# GatorLog.net
KiCad netlist of a schematic drawn in EAGLE
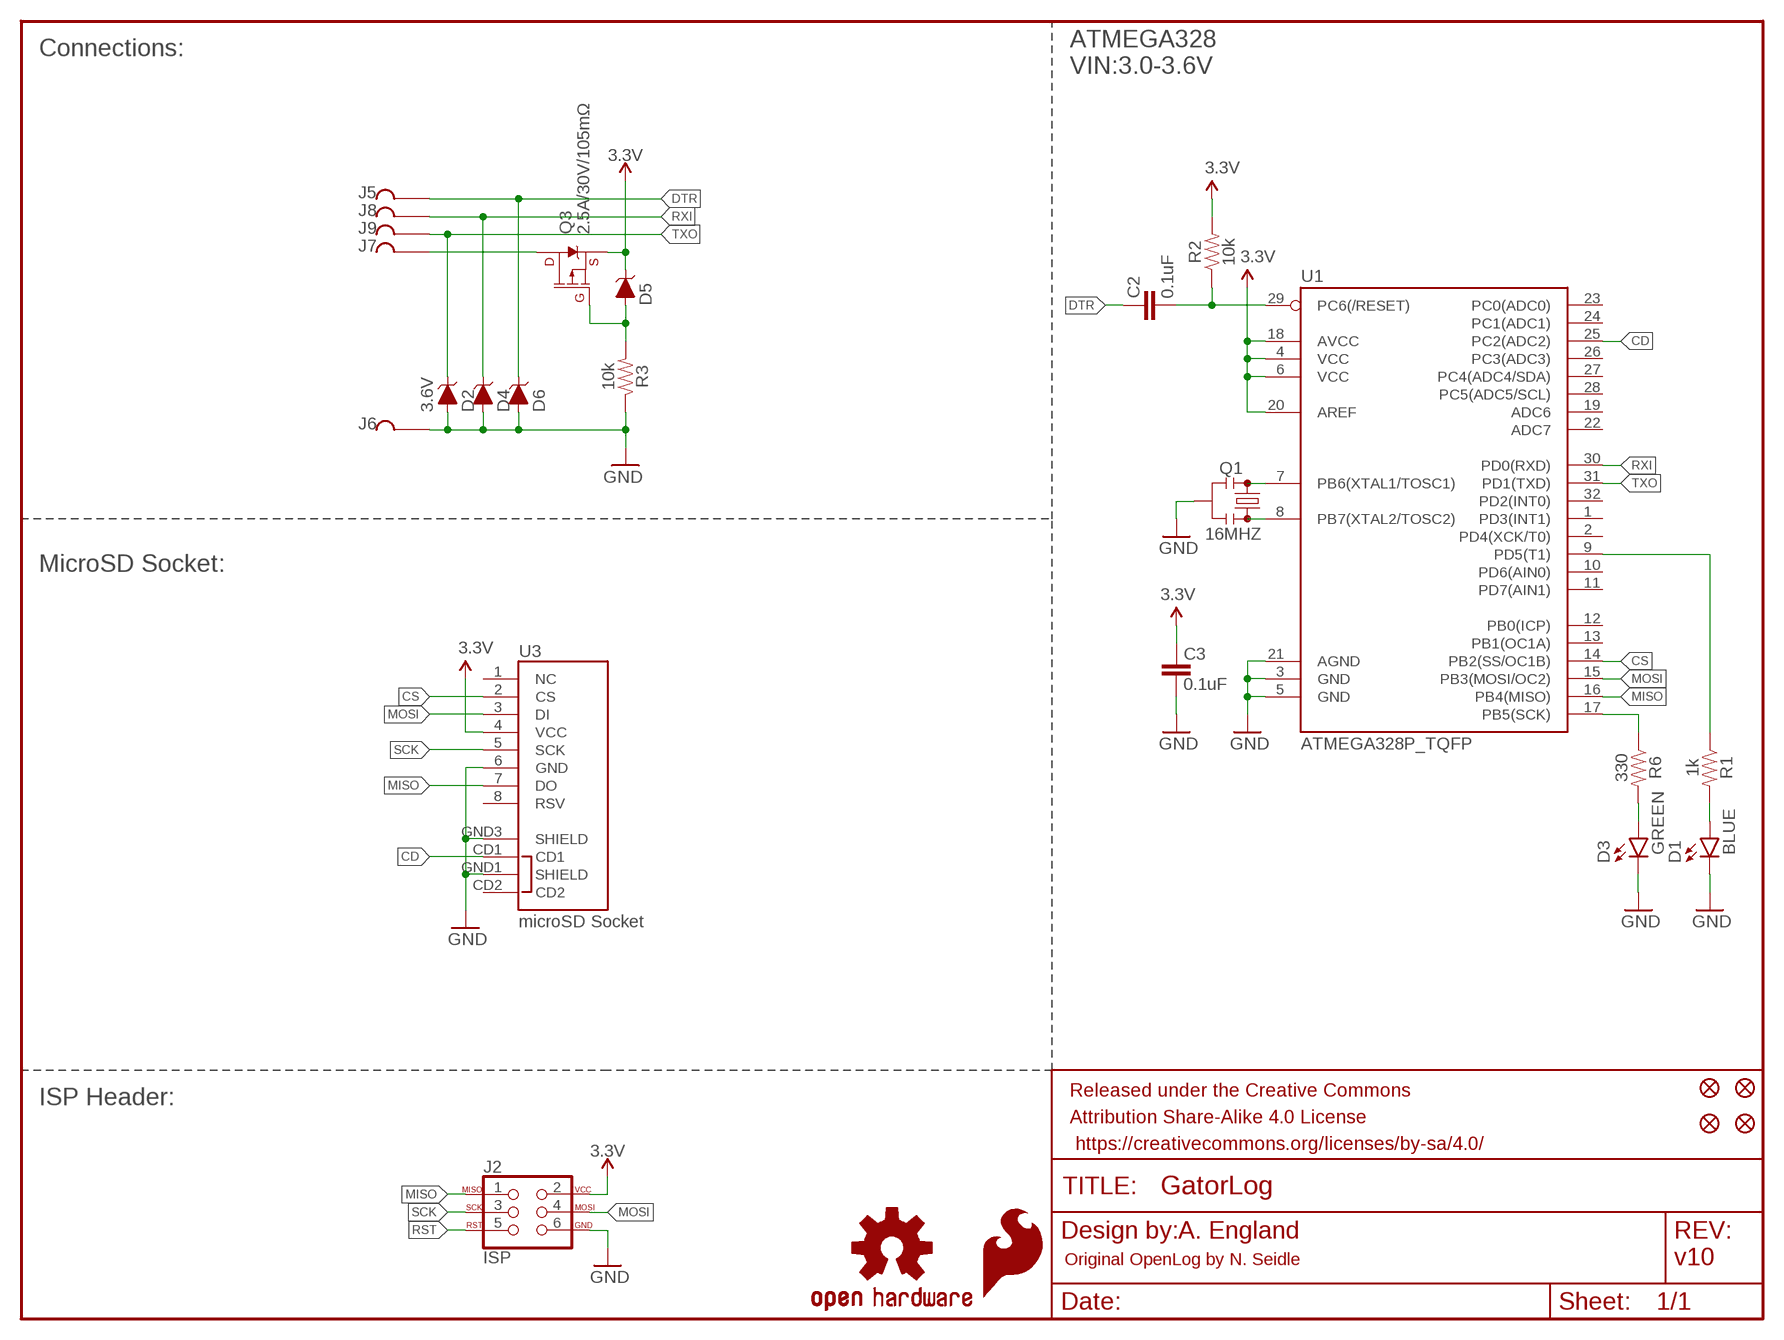
[diagram p0: schematic, sheet 1]

(export (version "E")
  (design (tool "Eeschema 10.0.6"))
  (components
    (comp (ref "C2")
      (value "0.1uF")
      (footprint "eagle-import:0603")
      (libsource (lib "eagle-import") (part "0.1UF-0603-25V-5%"))
    )
    (comp (ref "C3")
      (value "0.1uF")
      (footprint "eagle-import:0603")
      (libsource (lib "eagle-import") (part "0.1UF-0603-25V-5%"))
    )
    (comp (ref "D1")
      (value "BLUE")
      (footprint "eagle-import:LED-0603")
      (libsource (lib "eagle-import") (part "LED-BLUE0603"))
    )
    (comp (ref "D2")
      (value "3.6V")
      (footprint "eagle-import:SOD-323")
      (libsource (lib "eagle-import") (part "DIODE-ZENER-BZT52C3V6S"))
    )
    (comp (ref "D3")
      (value "GREEN")
      (footprint "eagle-import:LED-0603")
      (libsource (lib "eagle-import") (part "LED-GREEN0603"))
    )
    (comp (ref "D4")
      (value "3.6V")
      (footprint "eagle-import:SOD-323")
      (libsource (lib "eagle-import") (part "DIODE-ZENER-BZT52C3V6S"))
    )
    (comp (ref "D5")
      (value "3.6V")
      (footprint "eagle-import:SOD-323")
      (libsource (lib "eagle-import") (part "DIODE-ZENER-BZT52C3V6S"))
    )
    (comp (ref "D6")
      (value "3.6V")
      (footprint "eagle-import:SOD-323")
      (libsource (lib "eagle-import") (part "DIODE-ZENER-BZT52C3V6S"))
    )
    (comp (ref "FID1")
      (value "FIDUCIALUFIDUCIAL")
      (footprint "eagle-import:FIDUCIAL-MICRO")
      (libsource (lib "eagle-import") (part "FIDUCIALUFIDUCIAL"))
    )
    (comp (ref "FID2")
      (value "FIDUCIALUFIDUCIAL")
      (footprint "eagle-import:FIDUCIAL-MICRO")
      (libsource (lib "eagle-import") (part "FIDUCIALUFIDUCIAL"))
    )
    (comp (ref "FID3")
      (value "FIDUCIALUFIDUCIAL")
      (footprint "eagle-import:FIDUCIAL-MICRO")
      (libsource (lib "eagle-import") (part "FIDUCIALUFIDUCIAL"))
    )
    (comp (ref "FID4")
      (value "FIDUCIALUFIDUCIAL")
      (footprint "eagle-import:FIDUCIAL-MICRO")
      (libsource (lib "eagle-import") (part "FIDUCIALUFIDUCIAL"))
    )
    (comp (ref "FRAME1")
      (value "FRAME-LETTER")
      (footprint "eagle-import:CREATIVE_COMMONS")
      (libsource (lib "eagle-import") (part "FRAME-LETTER"))
    )
    (comp (ref "J2")
      (value "ISP")
      (footprint "eagle-import:2X3_TEST_POINTS")
      (libsource (lib "eagle-import") (part "AVR_SPI_PROG_3X2TESTPOINTS"))
    )
    (comp (ref "J5")
      (value "GATORGATOR_MINI")
      (footprint "eagle-import:GATOR_MINI")
      (libsource (lib "eagle-import") (part "GATORGATOR_MINI"))
    )
    (comp (ref "J6")
      (value "GATORGATOR_MINI")
      (footprint "eagle-import:GATOR_MINI")
      (libsource (lib "eagle-import") (part "GATORGATOR_MINI"))
    )
    (comp (ref "J7")
      (value "GATORGATOR_MINI")
      (footprint "eagle-import:GATOR_MINI")
      (libsource (lib "eagle-import") (part "GATORGATOR_MINI"))
    )
    (comp (ref "J8")
      (value "GATORGATOR_MINI")
      (footprint "eagle-import:GATOR_MINI")
      (libsource (lib "eagle-import") (part "GATORGATOR_MINI"))
    )
    (comp (ref "J9")
      (value "GATORGATOR_MINI")
      (footprint "eagle-import:GATOR_MINI")
      (libsource (lib "eagle-import") (part "GATORGATOR_MINI"))
    )
    (comp (ref "LOGO1")
      (value "SFE_LOGO_FLAME.1_INCH")
      (footprint "eagle-import:SFE_LOGO_FLAME_.1")
      (libsource (lib "eagle-import") (part "SFE_LOGO_FLAME.1_INCH"))
    )
    (comp (ref "LOGO2")
      (value "OSHW-LOGOMINI")
      (footprint "eagle-import:OSHW-LOGO-MINI")
      (libsource (lib "eagle-import") (part "OSHW-LOGOMINI"))
    )
    (comp (ref "Q1")
      (value "16MHZ")
      (footprint "eagle-import:RESONATOR-SMD")
      (libsource (lib "eagle-import") (part "RESONATOR16MHZ"))
    )
    (comp (ref "Q3")
      (value "2.5A/30V/105mΩ")
      (footprint "eagle-import:SOT23-3")
      (libsource (lib "eagle-import") (part "MOSFET_PCH-DMG2307L"))
    )
    (comp (ref "R1")
      (value "1k")
      (footprint "eagle-import:0603")
      (libsource (lib "eagle-import") (part "1KOHM-0603-1/10W-1%"))
    )
    (comp (ref "R2")
      (value "10k")
      (footprint "eagle-import:0603")
      (libsource (lib "eagle-import") (part "10KOHM-0603-1/10W-1%"))
    )
    (comp (ref "R3")
      (value "10k")
      (footprint "eagle-import:0603")
      (libsource (lib "eagle-import") (part "10KOHM-0603-1/10W-1%"))
    )
    (comp (ref "R6")
      (value "330")
      (footprint "eagle-import:0603")
      (libsource (lib "eagle-import") (part "330OHM-0603-1/10W-1%"))
    )
    (comp (ref "U1")
      (value "ATMEGA328P_TQFP")
      (footprint "eagle-import:TQFP32-08")
      (libsource (lib "eagle-import") (part "ATMEGA328P_TQFP"))
    )
    (comp (ref "U3")
      (value "microSD Socket")
      (footprint "eagle-import:MICROSD_1_1")
      (libsource (lib "eagle-import") (part "USD-SOCKET"))
    )
  )
  (nets
    (net (code "1") (name "3.3V") (class "Default")
      (node (ref "C3") (pin "2") (pinfunction "2_2") (pintype "passive"))
      (node (ref "D5") (pin "C") (pinfunction "C_C") (pintype "passive"))
      (node (ref "J2") (pin "2") (pinfunction "2_2") (pintype "passive"))
      (node (ref "Q3") (pin "2") (pinfunction "S_2") (pintype "bidirectional"))
      (node (ref "R2") (pin "2") (pinfunction "2_2") (pintype "passive"))
      (node (ref "U1") (pin "18") (pinfunction "AVCC_18") (pintype "bidirectional"))
      (node (ref "U1") (pin "20") (pinfunction "AREF_20") (pintype "bidirectional"))
      (node (ref "U1") (pin "4") (pinfunction "VCC_4") (pintype "bidirectional"))
      (node (ref "U1") (pin "6") (pinfunction "VCC_6") (pintype "bidirectional"))
      (node (ref "U3") (pin "4") (pinfunction "VCC_4") (pintype "bidirectional"))
    )
    (net (code "2") (name "CD") (class "Default")
      (node (ref "U1") (pin "25") (pinfunction "PC2(ADC2)_25") (pintype "bidirectional"))
      (node (ref "U3") (pin "CD1") (pinfunction "CD1_CD1") (pintype "bidirectional"))
    )
    (net (code "3") (name "CS") (class "Default")
      (node (ref "U1") (pin "14") (pinfunction "PB2(SS/OC1B)_14") (pintype "bidirectional"))
      (node (ref "U3") (pin "2") (pinfunction "CS_2") (pintype "bidirectional"))
    )
    (net (code "4") (name "DTR") (class "Default")
      (node (ref "C2") (pin "2") (pinfunction "2_2") (pintype "passive"))
      (node (ref "D6") (pin "C") (pinfunction "C_C") (pintype "passive"))
      (node (ref "J5") (pin "P$2") (pinfunction "P$1_P$2") (pintype "bidirectional"))
    )
    (net (code "5") (name "GND") (class "Default")
      (node (ref "C3") (pin "1") (pinfunction "1_1") (pintype "passive"))
      (node (ref "D1") (pin "C") (pinfunction "C_C") (pintype "passive"))
      (node (ref "D2") (pin "A") (pinfunction "A_A") (pintype "passive"))
      (node (ref "D3") (pin "C") (pinfunction "C_C") (pintype "passive"))
      (node (ref "D4") (pin "A") (pinfunction "A_A") (pintype "passive"))
      (node (ref "D6") (pin "A") (pinfunction "A_A") (pintype "passive"))
      (node (ref "J2") (pin "6") (pinfunction "6_6") (pintype "passive"))
      (node (ref "J6") (pin "P$2") (pinfunction "P$1_P$2") (pintype "bidirectional"))
      (node (ref "Q1") (pin "2") (pinfunction "2_2") (pintype "passive"))
      (node (ref "R3") (pin "1") (pinfunction "1_1") (pintype "passive"))
      (node (ref "U1") (pin "21") (pinfunction "AGND_21") (pintype "bidirectional"))
      (node (ref "U1") (pin "3") (pinfunction "GND_3") (pintype "bidirectional"))
      (node (ref "U1") (pin "5") (pinfunction "GND_5") (pintype "bidirectional"))
      (node (ref "U3") (pin "6") (pinfunction "GND_6") (pintype "bidirectional"))
      (node (ref "U3") (pin "GND1") (pinfunction "SHIELD_GND1") (pintype "bidirectional"))
      (node (ref "U3") (pin "GND3") (pinfunction "SHIELD_GND3") (pintype "bidirectional"))
    )
    (net (code "6") (name "MISO") (class "Default")
      (node (ref "J2") (pin "1") (pinfunction "1_1") (pintype "passive"))
      (node (ref "U1") (pin "16") (pinfunction "PB4(MISO)_16") (pintype "bidirectional"))
      (node (ref "U3") (pin "7") (pinfunction "DO_7") (pintype "bidirectional"))
    )
    (net (code "7") (name "MOSI") (class "Default")
      (node (ref "J2") (pin "4") (pinfunction "4_4") (pintype "passive"))
      (node (ref "U1") (pin "15") (pinfunction "PB3(MOSI/OC2)_15") (pintype "bidirectional"))
      (node (ref "U3") (pin "3") (pinfunction "DI_3") (pintype "bidirectional"))
    )
    (net (code "8") (name "Net-(D1-PadA)") (class "Default")
      (node (ref "D1") (pin "A") (pinfunction "A_A") (pintype "passive"))
      (node (ref "R1") (pin "2") (pinfunction "2_2") (pintype "passive"))
    )
    (net (code "9") (name "Net-(D3-PadA)") (class "Default")
      (node (ref "D3") (pin "A") (pinfunction "A_A") (pintype "passive"))
      (node (ref "R6") (pin "2") (pinfunction "2_2") (pintype "passive"))
    )
    (net (code "10") (name "Net-(J7-P$1)") (class "Default")
      (node (ref "J7") (pin "P$2") (pinfunction "P$1_P$2") (pintype "bidirectional"))
      (node (ref "Q3") (pin "3") (pinfunction "D_3") (pintype "bidirectional"))
    )
    (net (code "11") (name "Net-(Q3-G)") (class "Default")
      (node (ref "D5") (pin "A") (pinfunction "A_A") (pintype "passive"))
      (node (ref "Q3") (pin "1") (pinfunction "G_1") (pintype "bidirectional"))
      (node (ref "R3") (pin "2") (pinfunction "2_2") (pintype "passive"))
    )
    (net (code "12") (name "Net-(U1-PB6(XTAL1{slash}TOSC1))") (class "Default")
      (node (ref "Q1") (pin "3") (pinfunction "3_3") (pintype "passive"))
      (node (ref "U1") (pin "7") (pinfunction "PB6(XTAL1/TOSC1)_7") (pintype "bidirectional"))
    )
    (net (code "13") (name "Net-(U1-PB7(XTAL2{slash}TOSC2))") (class "Default")
      (node (ref "Q1") (pin "1") (pinfunction "1_1") (pintype "passive"))
      (node (ref "U1") (pin "8") (pinfunction "PB7(XTAL2/TOSC2)_8") (pintype "bidirectional"))
    )
    (net (code "14") (name "Net-(U1-PD5(T1))") (class "Default")
      (node (ref "R1") (pin "1") (pinfunction "1_1") (pintype "passive"))
      (node (ref "U1") (pin "9") (pinfunction "PD5(T1)_9") (pintype "bidirectional"))
    )
    (net (code "15") (name "RST") (class "Default")
      (node (ref "C2") (pin "1") (pinfunction "1_1") (pintype "passive"))
      (node (ref "J2") (pin "5") (pinfunction "5_5") (pintype "passive"))
      (node (ref "R2") (pin "1") (pinfunction "1_1") (pintype "passive"))
      (node (ref "U1") (pin "29") (pinfunction "PC6(/RESET)_29") (pintype "bidirectional"))
    )
    (net (code "16") (name "RXI") (class "Default")
      (node (ref "D4") (pin "C") (pinfunction "C_C") (pintype "passive"))
      (node (ref "J8") (pin "P$2") (pinfunction "P$1_P$2") (pintype "bidirectional"))
      (node (ref "U1") (pin "30") (pinfunction "PD0(RXD)_30") (pintype "bidirectional"))
    )
    (net (code "17") (name "SCK") (class "Default")
      (node (ref "J2") (pin "3") (pinfunction "3_3") (pintype "passive"))
      (node (ref "R6") (pin "1") (pinfunction "1_1") (pintype "passive"))
      (node (ref "U1") (pin "17") (pinfunction "PB5(SCK)_17") (pintype "bidirectional"))
      (node (ref "U3") (pin "5") (pinfunction "SCK_5") (pintype "bidirectional"))
    )
    (net (code "18") (name "TXO") (class "Default")
      (node (ref "D2") (pin "C") (pinfunction "C_C") (pintype "passive"))
      (node (ref "J9") (pin "P$2") (pinfunction "P$1_P$2") (pintype "bidirectional"))
      (node (ref "U1") (pin "31") (pinfunction "PD1(TXD)_31") (pintype "bidirectional"))
    )
    (net (code "19") (name "unconnected-(U1-ADC6-Pad19)") (class "Default")
      (node (ref "U1") (pin "19") (pinfunction "ADC6_19") (pintype "bidirectional"))
    )
    (net (code "20") (name "unconnected-(U1-ADC7-Pad22)") (class "Default")
      (node (ref "U1") (pin "22") (pinfunction "ADC7_22") (pintype "bidirectional"))
    )
    (net (code "21") (name "unconnected-(U1-PB0(ICP)-Pad12)") (class "Default")
      (node (ref "U1") (pin "12") (pinfunction "PB0(ICP)_12") (pintype "bidirectional"))
    )
    (net (code "22") (name "unconnected-(U1-PB1(OC1A)-Pad13)") (class "Default")
      (node (ref "U1") (pin "13") (pinfunction "PB1(OC1A)_13") (pintype "bidirectional"))
    )
    (net (code "23") (name "unconnected-(U1-PC0(ADC0)-Pad23)") (class "Default")
      (node (ref "U1") (pin "23") (pinfunction "PC0(ADC0)_23") (pintype "bidirectional"))
    )
    (net (code "24") (name "unconnected-(U1-PC1(ADC1)-Pad24)") (class "Default")
      (node (ref "U1") (pin "24") (pinfunction "PC1(ADC1)_24") (pintype "bidirectional"))
    )
    (net (code "25") (name "unconnected-(U1-PC3(ADC3)-Pad26)") (class "Default")
      (node (ref "U1") (pin "26") (pinfunction "PC3(ADC3)_26") (pintype "bidirectional"))
    )
    (net (code "26") (name "unconnected-(U1-PC4(ADC4{slash}SDA)-Pad27)") (class "Default")
      (node (ref "U1") (pin "27") (pinfunction "PC4(ADC4/SDA)_27") (pintype "bidirectional"))
    )
    (net (code "27") (name "unconnected-(U1-PC5(ADC5{slash}SCL)-Pad28)") (class "Default")
      (node (ref "U1") (pin "28") (pinfunction "PC5(ADC5/SCL)_28") (pintype "bidirectional"))
    )
    (net (code "28") (name "unconnected-(U1-PD2(INT0)-Pad32)") (class "Default")
      (node (ref "U1") (pin "32") (pinfunction "PD2(INT0)_32") (pintype "bidirectional"))
    )
    (net (code "29") (name "unconnected-(U1-PD3(INT1)-Pad1)") (class "Default")
      (node (ref "U1") (pin "1") (pinfunction "PD3(INT1)_1") (pintype "bidirectional"))
    )
    (net (code "30") (name "unconnected-(U1-PD4(XCK{slash}T0)-Pad2)") (class "Default")
      (node (ref "U1") (pin "2") (pinfunction "PD4(XCK/T0)_2") (pintype "bidirectional"))
    )
    (net (code "31") (name "unconnected-(U1-PD6(AIN0)-Pad10)") (class "Default")
      (node (ref "U1") (pin "10") (pinfunction "PD6(AIN0)_10") (pintype "bidirectional"))
    )
    (net (code "32") (name "unconnected-(U1-PD7(AIN1)-Pad11)") (class "Default")
      (node (ref "U1") (pin "11") (pinfunction "PD7(AIN1)_11") (pintype "bidirectional"))
    )
    (net (code "33") (name "unconnected-(U3-NC-Pad1)") (class "Default")
      (node (ref "U3") (pin "1") (pinfunction "NC_1") (pintype "bidirectional"))
    )
    (net (code "34") (name "unconnected-(U3-PadCD2)") (class "Default")
      (node (ref "U3") (pin "CD2") (pinfunction "CD2_CD2") (pintype "bidirectional"))
    )
    (net (code "35") (name "unconnected-(U3-RSV-Pad8)") (class "Default")
      (node (ref "U3") (pin "8") (pinfunction "RSV_8") (pintype "bidirectional"))
    )
  )
)
